# PhotodiodeDaughter.net
KiCad netlist of a schematic drawn in EAGLE
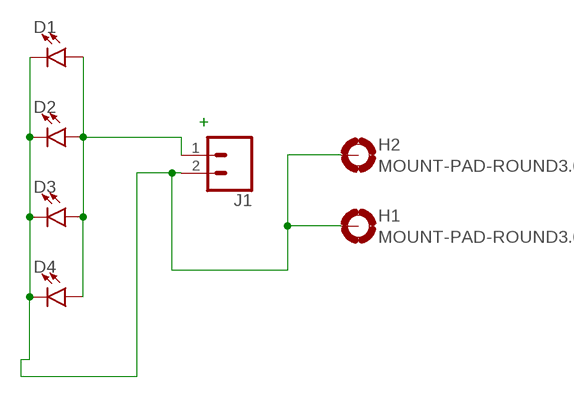
[diagram p0: schematic, sheet 1]

(export (version "E")
  (design (tool "Eeschema 10.0.6"))
  (components
    (comp (ref "D1")
      (value "LED3MM")
      (footprint "eagle-import:LED_3MM")
      (libsource (lib "eagle-import") (part "LED3MM"))
    )
    (comp (ref "D2")
      (value "LED3MM")
      (footprint "eagle-import:LED_3MM")
      (libsource (lib "eagle-import") (part "LED3MM"))
    )
    (comp (ref "D3")
      (value "LED3MM")
      (footprint "eagle-import:LED_3MM")
      (libsource (lib "eagle-import") (part "LED3MM"))
    )
    (comp (ref "D4")
      (value "LED3MM")
      (footprint "eagle-import:LED_3MM")
      (libsource (lib "eagle-import") (part "LED3MM"))
    )
    (comp (ref "H1")
      (value "MOUNT-PAD-ROUND3.6")
      (footprint "eagle-import:3,6-PAD")
      (libsource (lib "eagle-import") (part "MOUNT-PAD-ROUND3.6"))
    )
    (comp (ref "H2")
      (value "MOUNT-PAD-ROUND3.6")
      (footprint "eagle-import:3,6-PAD")
      (libsource (lib "eagle-import") (part "MOUNT-PAD-ROUND3.6"))
    )
    (comp (ref "J1")
      (value "CONN_02")
      (footprint "eagle-import:1X02")
      (libsource (lib "eagle-import") (part "CONN_02"))
    )
  )
  (nets
    (net (code "1") (name "Net-(D1-C)") (class "Default")
      (node (ref "D1") (pin "K") (pinfunction "C_K") (pintype "passive"))
      (node (ref "D2") (pin "K") (pinfunction "C_K") (pintype "passive"))
      (node (ref "D3") (pin "K") (pinfunction "C_K") (pintype "passive"))
      (node (ref "D4") (pin "K") (pinfunction "C_K") (pintype "passive"))
      (node (ref "H1") (pin "B3,6") (pinfunction "MOUNT_B3,6") (pintype "passive"))
      (node (ref "H2") (pin "B3,6") (pinfunction "MOUNT_B3,6") (pintype "passive"))
      (node (ref "J1") (pin "2") (pinfunction "2_2") (pintype "passive"))
    )
    (net (code "2") (name "Net-(D1-PadA)") (class "Default")
      (node (ref "D1") (pin "A") (pinfunction "A_A") (pintype "passive"))
      (node (ref "D2") (pin "A") (pinfunction "A_A") (pintype "passive"))
      (node (ref "D3") (pin "A") (pinfunction "A_A") (pintype "passive"))
      (node (ref "D4") (pin "A") (pinfunction "A_A") (pintype "passive"))
      (node (ref "J1") (pin "1") (pinfunction "1_1") (pintype "passive"))
    )
  )
)
